# hackspace_con.net
KiCad netlist of a schematic drawn in EAGLE
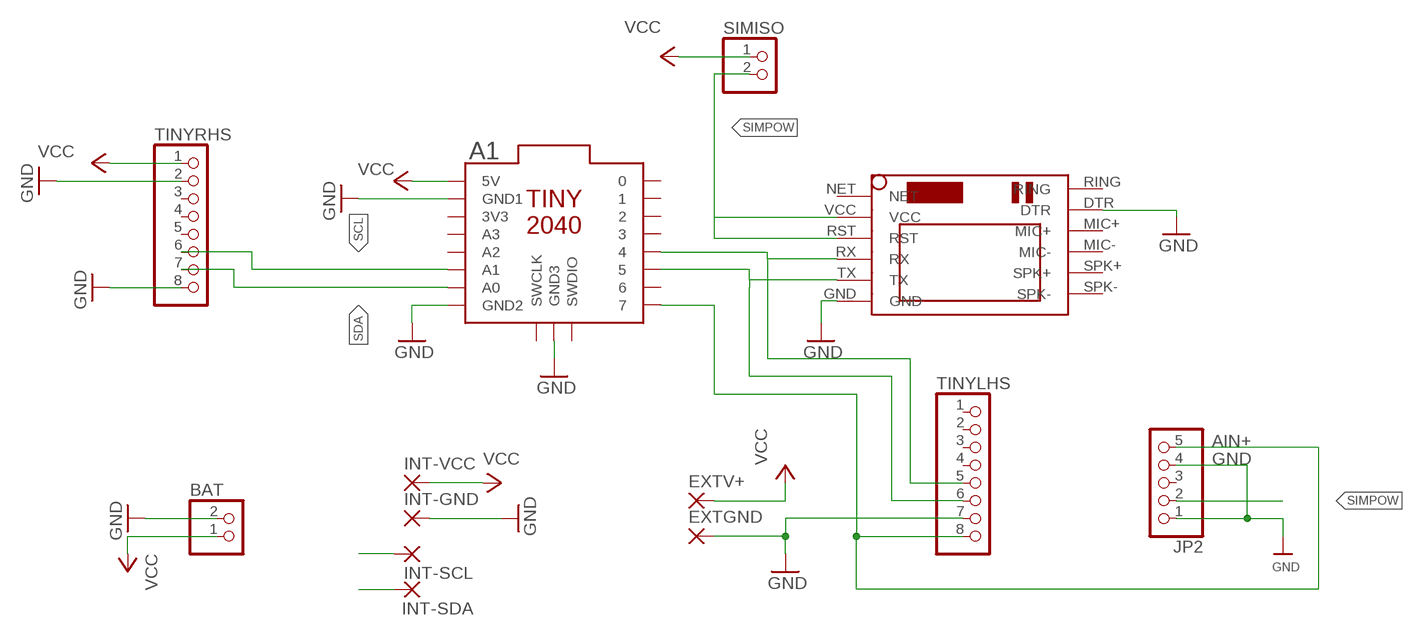
[diagram p0: schematic, sheet 1]

(export (version "E")
  (design (tool "Eeschema 10.0.6"))
  (components
    (comp (ref "A1")
      (value "TINY2040")
      (footprint "eagle-import:TINY2040")
      (libsource (lib "eagle-import") (part "TINY2040"))
    )
    (comp (ref "BAT")
      (value "JST_2PIN-THM-RA")
      (footprint "eagle-import:JST-PH-2-THM-RA")
      (libsource (lib "eagle-import") (part "JST_2PIN-THM-RA"))
    )
    (comp (ref "EXTGND")
      (value "SMD5")
      (footprint "eagle-import:SMD2,54-5,08")
      (libsource (lib "eagle-import") (part "SMD5"))
    )
    (comp (ref "EXTV+")
      (value "SMD5")
      (footprint "eagle-import:SMD2,54-5,08")
      (libsource (lib "eagle-import") (part "SMD5"))
    )
    (comp (ref "INT-GND")
      (value "3,17/1,1")
      (footprint "eagle-import:3,17_1,1")
      (libsource (lib "eagle-import") (part "3,17/1,1"))
    )
    (comp (ref "INT-SCL")
      (value "3,17/1,1")
      (footprint "eagle-import:3,17_1,1")
      (libsource (lib "eagle-import") (part "3,17/1,1"))
    )
    (comp (ref "INT-SDA")
      (value "3,17/1,1")
      (footprint "eagle-import:3,17_1,1")
      (libsource (lib "eagle-import") (part "3,17/1,1"))
    )
    (comp (ref "INT-VCC")
      (value "3,17/1,1")
      (footprint "eagle-import:3,17_1,1")
      (libsource (lib "eagle-import") (part "3,17/1,1"))
    )
    (comp (ref "JP2")
      (value "HEADER-1X570MIL")
      (footprint "eagle-import:1X05_ROUND_70")
      (libsource (lib "eagle-import") (part "HEADER-1X570MIL"))
    )
    (comp (ref "SIMISO")
      (value "PINHD-1X2")
      (footprint "eagle-import:1X02")
      (libsource (lib "eagle-import") (part "PINHD-1X2"))
    )
    (comp (ref "TINYLHS")
      (value "PINHD-1X8")
      (footprint "eagle-import:1X08")
      (libsource (lib "eagle-import") (part "PINHD-1X8"))
    )
    (comp (ref "TINYRHS")
      (value "PINHD-1X8")
      (footprint "eagle-import:1X08")
      (libsource (lib "eagle-import") (part "PINHD-1X8"))
    )
    (comp (ref "U$1")
      (value "SIM800LMODULE")
      (footprint "eagle-import:SIM800LMODULE")
      (libsource (lib "eagle-import") (part "SIM800LMODULE"))
    )
  )
  (nets
    (net (code "1") (name "/AIN+") (class "Default")
      (node (ref "A1") (pin "7") (pinfunction "7_7") (pintype "bidirectional"))
      (node (ref "JP2") (pin "5") (pinfunction "5_5") (pintype "passive"))
      (node (ref "TINYLHS") (pin "8") (pinfunction "8_8") (pintype "passive"))
    )
    (net (code "2") (name "GND") (class "Default")
      (node (ref "A1") (pin "GND1") (pinfunction "GND1_GND1") (pintype "bidirectional"))
      (node (ref "A1") (pin "GND2") (pinfunction "GND2_GND2") (pintype "bidirectional"))
      (node (ref "A1") (pin "GND3") (pinfunction "GND3_GND3") (pintype "bidirectional"))
      (node (ref "BAT") (pin "2") (pinfunction "1_2") (pintype "passive"))
      (node (ref "EXTGND") (pin "1") (pinfunction "P_1") (pintype "passive"))
      (node (ref "INT-GND") (pin "1") (pinfunction "P_1") (pintype "passive"))
      (node (ref "JP2") (pin "1") (pinfunction "1_1") (pintype "passive"))
      (node (ref "JP2") (pin "4") (pinfunction "4_4") (pintype "passive"))
      (node (ref "TINYLHS") (pin "7") (pinfunction "7_7") (pintype "passive"))
      (node (ref "TINYRHS") (pin "2") (pinfunction "2_2") (pintype "passive"))
      (node (ref "TINYRHS") (pin "8") (pinfunction "8_8") (pintype "passive"))
      (node (ref "U$1") (pin "DTR") (pinfunction "DTR_DTR") (pintype "bidirectional"))
      (node (ref "U$1") (pin "GND") (pinfunction "GND_GND") (pintype "bidirectional"))
    )
    (net (code "3") (name "Net-(A1-Pad4)") (class "Default")
      (node (ref "A1") (pin "4") (pinfunction "4_4") (pintype "bidirectional"))
      (node (ref "TINYLHS") (pin "5") (pinfunction "5_5") (pintype "passive"))
      (node (ref "U$1") (pin "RX") (pinfunction "RX_RX") (pintype "bidirectional"))
    )
    (net (code "4") (name "Net-(A1-Pad5)") (class "Default")
      (node (ref "A1") (pin "5") (pinfunction "5_5") (pintype "bidirectional"))
      (node (ref "TINYLHS") (pin "6") (pinfunction "6_6") (pintype "passive"))
      (node (ref "U$1") (pin "TX") (pinfunction "TX_TX") (pintype "bidirectional"))
    )
    (net (code "5") (name "SCL") (class "Default")
      (node (ref "A1") (pin "A1") (pinfunction "A1_A1") (pintype "bidirectional"))
      (node (ref "INT-SCL") (pin "1") (pinfunction "P_1") (pintype "passive"))
      (node (ref "TINYRHS") (pin "6") (pinfunction "6_6") (pintype "passive"))
    )
    (net (code "6") (name "SDA") (class "Default")
      (node (ref "A1") (pin "A0") (pinfunction "A0_A0") (pintype "bidirectional"))
      (node (ref "INT-SDA") (pin "1") (pinfunction "P_1") (pintype "passive"))
      (node (ref "TINYRHS") (pin "7") (pinfunction "7_7") (pintype "passive"))
    )
    (net (code "7") (name "SIMPOW") (class "Default")
      (node (ref "JP2") (pin "2") (pinfunction "2_2") (pintype "passive"))
      (node (ref "SIMISO") (pin "2") (pinfunction "2_2") (pintype "passive"))
      (node (ref "U$1") (pin "RST") (pinfunction "RST_RST") (pintype "bidirectional"))
      (node (ref "U$1") (pin "VCC") (pinfunction "VCC_VCC") (pintype "bidirectional"))
    )
    (net (code "8") (name "VCC") (class "Default")
      (node (ref "A1") (pin "5V") (pinfunction "5V_5V") (pintype "bidirectional"))
      (node (ref "BAT") (pin "1") (pinfunction "2_1") (pintype "passive"))
      (node (ref "EXTV+") (pin "1") (pinfunction "P_1") (pintype "passive"))
      (node (ref "INT-VCC") (pin "1") (pinfunction "P_1") (pintype "passive"))
      (node (ref "SIMISO") (pin "1") (pinfunction "1_1") (pintype "passive"))
      (node (ref "TINYRHS") (pin "1") (pinfunction "1_1") (pintype "passive"))
    )
    (net (code "9") (name "unconnected-(A1-Pad0)") (class "Default")
      (node (ref "A1") (pin "0") (pinfunction "0_0") (pintype "bidirectional"))
    )
    (net (code "10") (name "unconnected-(A1-Pad1)") (class "Default")
      (node (ref "A1") (pin "1") (pinfunction "1_1") (pintype "bidirectional"))
    )
    (net (code "11") (name "unconnected-(A1-Pad2)") (class "Default")
      (node (ref "A1") (pin "2") (pinfunction "2_2") (pintype "bidirectional"))
    )
    (net (code "12") (name "unconnected-(A1-Pad3)") (class "Default")
      (node (ref "A1") (pin "3") (pinfunction "3_3") (pintype "bidirectional"))
    )
    (net (code "13") (name "unconnected-(A1-Pad3V3)") (class "Default")
      (node (ref "A1") (pin "3V3") (pinfunction "3V3_3V3") (pintype "bidirectional"))
    )
    (net (code "14") (name "unconnected-(A1-Pad6)") (class "Default")
      (node (ref "A1") (pin "6") (pinfunction "6_6") (pintype "bidirectional"))
    )
    (net (code "15") (name "unconnected-(A1-PadA2)") (class "Default")
      (node (ref "A1") (pin "A2") (pinfunction "A2_A2") (pintype "bidirectional"))
    )
    (net (code "16") (name "unconnected-(A1-PadA3)") (class "Default")
      (node (ref "A1") (pin "A3") (pinfunction "A3_A3") (pintype "bidirectional"))
    )
    (net (code "17") (name "unconnected-(A1-PadSWCLK)") (class "Default")
      (node (ref "A1") (pin "SWCLK") (pinfunction "SWCLK_SWCLK") (pintype "bidirectional"))
    )
    (net (code "18") (name "unconnected-(A1-PadSWDIO)") (class "Default")
      (node (ref "A1") (pin "SWDIO") (pinfunction "SWDIO_SWDIO") (pintype "bidirectional"))
    )
    (net (code "19") (name "unconnected-(JP2-Pad3)") (class "Default")
      (node (ref "JP2") (pin "3") (pinfunction "3_3") (pintype "passive"))
    )
    (net (code "20") (name "unconnected-(TINYLHS-Pad1)") (class "Default")
      (node (ref "TINYLHS") (pin "1") (pinfunction "1_1") (pintype "passive"))
    )
    (net (code "21") (name "unconnected-(TINYLHS-Pad2)") (class "Default")
      (node (ref "TINYLHS") (pin "2") (pinfunction "2_2") (pintype "passive"))
    )
    (net (code "22") (name "unconnected-(TINYLHS-Pad3)") (class "Default")
      (node (ref "TINYLHS") (pin "3") (pinfunction "3_3") (pintype "passive"))
    )
    (net (code "23") (name "unconnected-(TINYLHS-Pad4)") (class "Default")
      (node (ref "TINYLHS") (pin "4") (pinfunction "4_4") (pintype "passive"))
    )
    (net (code "24") (name "unconnected-(TINYRHS-Pad3)") (class "Default")
      (node (ref "TINYRHS") (pin "3") (pinfunction "3_3") (pintype "passive"))
    )
    (net (code "25") (name "unconnected-(TINYRHS-Pad4)") (class "Default")
      (node (ref "TINYRHS") (pin "4") (pinfunction "4_4") (pintype "passive"))
    )
    (net (code "26") (name "unconnected-(TINYRHS-Pad5)") (class "Default")
      (node (ref "TINYRHS") (pin "5") (pinfunction "5_5") (pintype "passive"))
    )
    (net (code "27") (name "unconnected-(U$1-PadMIC+)") (class "Default")
      (node (ref "U$1") (pin "MIC+") (pinfunction "MIC+_MIC+") (pintype "bidirectional"))
    )
    (net (code "28") (name "unconnected-(U$1-PadMIC-)") (class "Default")
      (node (ref "U$1") (pin "MIC-") (pinfunction "MIC-_MIC-") (pintype "bidirectional"))
    )
    (net (code "29") (name "unconnected-(U$1-PadNET)") (class "Default")
      (node (ref "U$1") (pin "NET") (pinfunction "NET_NET") (pintype "bidirectional"))
    )
    (net (code "30") (name "unconnected-(U$1-PadRING)") (class "Default")
      (node (ref "U$1") (pin "RING") (pinfunction "RING_RING") (pintype "bidirectional"))
    )
    (net (code "31") (name "unconnected-(U$1-PadSPK+)") (class "Default")
      (node (ref "U$1") (pin "SPK+") (pinfunction "SPK+_SPK+") (pintype "bidirectional"))
    )
    (net (code "32") (name "unconnected-(U$1-PadSPK-)") (class "Default")
      (node (ref "U$1") (pin "SPK-") (pinfunction "SPK-_SPK-") (pintype "bidirectional"))
    )
  )
)
